# Display_Pitch.net
KiCad netlist of a schematic drawn in Altium Designer
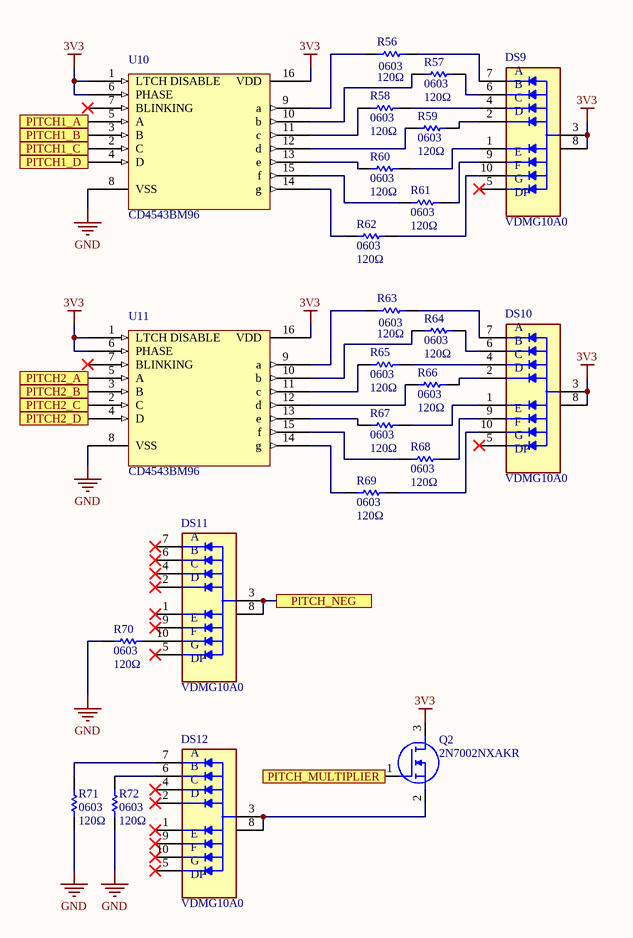
[diagram p0: Display Pitch.SchDoc]

(export (version "E")
  (design (tool "Eeschema 10.0.6"))
  (components
    (comp (ref "DS9")
      (value "VDMG10A0")
      (footprint "DISPLAY_VDMG10A0")
      (description "Smart/Normal 7 Seg Numeric LED Display")
      (fields (field (name "MANUFACTURER") "Vishay Semiconductors"))
      (libsource (lib "SKALE_LIB") (part "7 SEG DISPLAY - VDMG10A0"))
    )
    (comp (ref "DS10")
      (value "VDMG10A0")
      (footprint "DISPLAY_VDMG10A0")
      (description "Smart/Normal 7 Seg Numeric LED Display")
      (fields (field (name "MANUFACTURER") "Vishay Semiconductors"))
      (libsource (lib "SKALE_LIB") (part "7 SEG DISPLAY - VDMG10A0"))
    )
    (comp (ref "DS11")
      (value "VDMG10A0")
      (footprint "DISPLAY_VDMG10A0")
      (description "Smart/Normal 7 Seg Numeric LED Display")
      (fields (field (name "MANUFACTURER") "Vishay Semiconductors"))
      (libsource (lib "SKALE_LIB") (part "7 SEG DISPLAY - VDMG10A0"))
    )
    (comp (ref "DS12")
      (value "VDMG10A0")
      (footprint "DISPLAY_VDMG10A0")
      (description "Smart/Normal 7 Seg Numeric LED Display")
      (fields (field (name "MANUFACTURER") "Vishay Semiconductors"))
      (libsource (lib "SKALE_LIB") (part "7 SEG DISPLAY - VDMG10A0"))
    )
    (comp (ref "Q2")
      (value "2N7002NXAKR")
      (footprint "SKALE_LIB:TO-236AB")
      (description "Transistor Mosfet N-ch 60V 0.3A 3-PIN TO-263AB T/r")
      (fields (field (name "MF") "Nexperia USA Inc.") (field (name "MANUFACTURER") "Nexperia"))
      (libsource (lib "SKALE_LIB") (part "MOSFET N-60V-190mA"))
    )
    (comp (ref "R56")
      (value "120Ω")
      (footprint "RES0603")
      (description "RES 120 OHM 5% 1/10W 0603")
      (fields (field (name "PACKAGE/FOOTPRINT") "0603") (field (name "Comment") "RES_120Ω_0603"))
      (libsource (lib "SKALE_LIB") (part "RES_120Ω_0603_5%"))
    )
    (comp (ref "R57")
      (value "120Ω")
      (footprint "RES0603")
      (description "RES 120 OHM 5% 1/10W 0603")
      (fields (field (name "PACKAGE/FOOTPRINT") "0603") (field (name "Comment") "RES_120Ω_0603"))
      (libsource (lib "SKALE_LIB") (part "RES_120Ω_0603_5%"))
    )
    (comp (ref "R58")
      (value "120Ω")
      (footprint "RES0603")
      (description "RES 120 OHM 5% 1/10W 0603")
      (fields (field (name "PACKAGE/FOOTPRINT") "0603") (field (name "Comment") "RES_120Ω_0603"))
      (libsource (lib "SKALE_LIB") (part "RES_120Ω_0603_5%"))
    )
    (comp (ref "R59")
      (value "120Ω")
      (footprint "RES0603")
      (description "RES 120 OHM 5% 1/10W 0603")
      (fields (field (name "PACKAGE/FOOTPRINT") "0603") (field (name "Comment") "RES_120Ω_0603"))
      (libsource (lib "SKALE_LIB") (part "RES_120Ω_0603_5%"))
    )
    (comp (ref "R60")
      (value "120Ω")
      (footprint "RES0603")
      (description "RES 120 OHM 5% 1/10W 0603")
      (fields (field (name "PACKAGE/FOOTPRINT") "0603") (field (name "Comment") "RES_120Ω_0603"))
      (libsource (lib "SKALE_LIB") (part "RES_120Ω_0603_5%"))
    )
    (comp (ref "R61")
      (value "120Ω")
      (footprint "RES0603")
      (description "RES 120 OHM 5% 1/10W 0603")
      (fields (field (name "PACKAGE/FOOTPRINT") "0603") (field (name "Comment") "RES_120Ω_0603"))
      (libsource (lib "SKALE_LIB") (part "RES_120Ω_0603_5%"))
    )
    (comp (ref "R62")
      (value "120Ω")
      (footprint "RES0603")
      (description "RES 120 OHM 5% 1/10W 0603")
      (fields (field (name "PACKAGE/FOOTPRINT") "0603") (field (name "Comment") "RES_120Ω_0603"))
      (libsource (lib "SKALE_LIB") (part "RES_120Ω_0603_5%"))
    )
    (comp (ref "R63")
      (value "120Ω")
      (footprint "RES0603")
      (description "RES 120 OHM 5% 1/10W 0603")
      (fields (field (name "PACKAGE/FOOTPRINT") "0603") (field (name "Comment") "RES_120Ω_0603"))
      (libsource (lib "SKALE_LIB") (part "RES_120Ω_0603_5%"))
    )
    (comp (ref "R64")
      (value "120Ω")
      (footprint "RES0603")
      (description "RES 120 OHM 5% 1/10W 0603")
      (fields (field (name "PACKAGE/FOOTPRINT") "0603") (field (name "Comment") "RES_120Ω_0603"))
      (libsource (lib "SKALE_LIB") (part "RES_120Ω_0603_5%"))
    )
    (comp (ref "R65")
      (value "120Ω")
      (footprint "RES0603")
      (description "RES 120 OHM 5% 1/10W 0603")
      (fields (field (name "PACKAGE/FOOTPRINT") "0603") (field (name "Comment") "RES_120Ω_0603"))
      (libsource (lib "SKALE_LIB") (part "RES_120Ω_0603_5%"))
    )
    (comp (ref "R66")
      (value "120Ω")
      (footprint "RES0603")
      (description "RES 120 OHM 5% 1/10W 0603")
      (fields (field (name "PACKAGE/FOOTPRINT") "0603") (field (name "Comment") "RES_120Ω_0603"))
      (libsource (lib "SKALE_LIB") (part "RES_120Ω_0603_5%"))
    )
    (comp (ref "R67")
      (value "120Ω")
      (footprint "RES0603")
      (description "RES 120 OHM 5% 1/10W 0603")
      (fields (field (name "PACKAGE/FOOTPRINT") "0603") (field (name "Comment") "RES_120Ω_0603"))
      (libsource (lib "SKALE_LIB") (part "RES_120Ω_0603_5%"))
    )
    (comp (ref "R68")
      (value "120Ω")
      (footprint "RES0603")
      (description "RES 120 OHM 5% 1/10W 0603")
      (fields (field (name "PACKAGE/FOOTPRINT") "0603") (field (name "Comment") "RES_120Ω_0603"))
      (libsource (lib "SKALE_LIB") (part "RES_120Ω_0603_5%"))
    )
    (comp (ref "R69")
      (value "120Ω")
      (footprint "RES0603")
      (description "RES 120 OHM 5% 1/10W 0603")
      (fields (field (name "PACKAGE/FOOTPRINT") "0603") (field (name "Comment") "RES_120Ω_0603"))
      (libsource (lib "SKALE_LIB") (part "RES_120Ω_0603_5%"))
    )
    (comp (ref "R70")
      (value "120Ω")
      (footprint "RES0603")
      (description "RES 120 OHM 5% 1/10W 0603")
      (fields (field (name "PACKAGE/FOOTPRINT") "0603") (field (name "Comment") "RES_120Ω_0603"))
      (libsource (lib "SKALE_LIB") (part "RES_120Ω_0603_5%"))
    )
    (comp (ref "R71")
      (value "120Ω")
      (footprint "RES0603")
      (description "RES 120 OHM 5% 1/10W 0603")
      (fields (field (name "PACKAGE/FOOTPRINT") "0603") (field (name "Comment") "RES_120Ω_0603"))
      (libsource (lib "SKALE_LIB") (part "RES_120Ω_0603_5%"))
    )
    (comp (ref "R72")
      (value "120Ω")
      (footprint "RES0603")
      (description "RES 120 OHM 5% 1/10W 0603")
      (fields (field (name "PACKAGE/FOOTPRINT") "0603") (field (name "Comment") "RES_120Ω_0603"))
      (libsource (lib "SKALE_LIB") (part "RES_120Ω_0603_5%"))
    )
    (comp (ref "U10")
      (value "CD4543BM96")
      (footprint "SOIC127P600X175-16N")
      (description "Seven Segment Decoder/Driver, 4000/14000/40000 Series, Configurable Output, CMOS, PDSO16")
      (fields (field (name "MANUFACTURER") "Texas Instruments"))
      (libsource (lib "SKALE_LIB") (part "7 SEG DISPLAY IC"))
    )
    (comp (ref "U11")
      (value "CD4543BM96")
      (footprint "SOIC127P600X175-16N")
      (description "Seven Segment Decoder/Driver, 4000/14000/40000 Series, Configurable Output, CMOS, PDSO16")
      (fields (field (name "MANUFACTURER") "Texas Instruments"))
      (libsource (lib "SKALE_LIB") (part "7 SEG DISPLAY IC"))
    )
  )
  (nets
    (net (code "1") (name "/PITCH1_A") (class "Default")
      (node (ref "U10") (pin "5") (pinfunction "A_5") (pintype "input"))
    )
    (net (code "2") (name "/PITCH1_B") (class "Default")
      (node (ref "U10") (pin "3") (pinfunction "B_3") (pintype "input"))
    )
    (net (code "3") (name "/PITCH1_C") (class "Default")
      (node (ref "U10") (pin "2") (pinfunction "C_2") (pintype "input"))
    )
    (net (code "4") (name "/PITCH1_D") (class "Default")
      (node (ref "U10") (pin "4") (pinfunction "D_4") (pintype "input"))
    )
    (net (code "5") (name "/PITCH2_A") (class "Default")
      (node (ref "U11") (pin "5") (pinfunction "A_5") (pintype "input"))
    )
    (net (code "6") (name "/PITCH2_B") (class "Default")
      (node (ref "U11") (pin "3") (pinfunction "B_3") (pintype "input"))
    )
    (net (code "7") (name "/PITCH2_C") (class "Default")
      (node (ref "U11") (pin "2") (pinfunction "C_2") (pintype "input"))
    )
    (net (code "8") (name "/PITCH2_D") (class "Default")
      (node (ref "U11") (pin "4") (pinfunction "D_4") (pintype "input"))
    )
    (net (code "9") (name "/PITCH_MULTIPLIER") (class "Default")
      (node (ref "Q2") (pin "1") (pinfunction "G_1") (pintype "bidirectional"))
    )
    (net (code "10") (name "/PITCH_NEG") (class "Default")
      (node (ref "DS11") (pin "3") (pinfunction "ANODE_3") (pintype "passive"))
      (node (ref "DS11") (pin "8") (pinfunction "ANODE_8") (pintype "passive"))
    )
    (net (code "11") (name "3V3") (class "Default")
      (node (ref "DS10") (pin "3") (pinfunction "ANODE_3") (pintype "passive"))
      (node (ref "DS10") (pin "8") (pinfunction "ANODE_8") (pintype "passive"))
      (node (ref "DS9") (pin "3") (pinfunction "ANODE_3") (pintype "passive"))
      (node (ref "DS9") (pin "8") (pinfunction "ANODE_8") (pintype "passive"))
      (node (ref "Q2") (pin "3") (pinfunction "D_3") (pintype "bidirectional"))
      (node (ref "U10") (pin "1") (pinfunction "LTCH_DISABLE_1") (pintype "input"))
      (node (ref "U10") (pin "16") (pinfunction "VDD_16") (pintype "power_in"))
      (node (ref "U10") (pin "6") (pinfunction "PHASE_6") (pintype "input"))
      (node (ref "U11") (pin "1") (pinfunction "LTCH_DISABLE_1") (pintype "input"))
      (node (ref "U11") (pin "16") (pinfunction "VDD_16") (pintype "power_in"))
      (node (ref "U11") (pin "6") (pinfunction "PHASE_6") (pintype "input"))
    )
    (net (code "12") (name "GND") (class "Default")
      (node (ref "R70") (pin "1") (pinfunction "1_1") (pintype "passive"))
      (node (ref "R71") (pin "1") (pinfunction "1_1") (pintype "passive"))
      (node (ref "R72") (pin "1") (pinfunction "1_1") (pintype "passive"))
      (node (ref "U10") (pin "8") (pinfunction "VSS_8") (pintype "power_in"))
      (node (ref "U11") (pin "8") (pinfunction "VSS_8") (pintype "power_in"))
    )
    (net (code "13") (name "Net-(DS9-A)") (class "Default")
      (node (ref "DS9") (pin "7") (pinfunction "A_7") (pintype "passive"))
      (node (ref "R56") (pin "2") (pinfunction "2_2") (pintype "passive"))
    )
    (net (code "14") (name "Net-(DS9-B)") (class "Default")
      (node (ref "DS9") (pin "6") (pinfunction "B_6") (pintype "passive"))
      (node (ref "R57") (pin "2") (pinfunction "2_2") (pintype "passive"))
    )
    (net (code "15") (name "Net-(DS9-C)") (class "Default")
      (node (ref "DS9") (pin "4") (pinfunction "C_4") (pintype "passive"))
      (node (ref "R58") (pin "2") (pinfunction "2_2") (pintype "passive"))
    )
    (net (code "16") (name "Net-(DS9-D)") (class "Default")
      (node (ref "DS9") (pin "2") (pinfunction "D_2") (pintype "passive"))
      (node (ref "R59") (pin "2") (pinfunction "2_2") (pintype "passive"))
    )
    (net (code "17") (name "Net-(DS9-E)") (class "Default")
      (node (ref "DS9") (pin "1") (pinfunction "E_1") (pintype "passive"))
      (node (ref "R60") (pin "2") (pinfunction "2_2") (pintype "passive"))
    )
    (net (code "18") (name "Net-(DS9-F)") (class "Default")
      (node (ref "DS9") (pin "9") (pinfunction "F_9") (pintype "passive"))
      (node (ref "R61") (pin "2") (pinfunction "2_2") (pintype "passive"))
    )
    (net (code "19") (name "Net-(DS9-G)") (class "Default")
      (node (ref "DS9") (pin "10") (pinfunction "G_10") (pintype "passive"))
      (node (ref "R62") (pin "2") (pinfunction "2_2") (pintype "passive"))
    )
    (net (code "20") (name "Net-(DS10-A)") (class "Default")
      (node (ref "DS10") (pin "7") (pinfunction "A_7") (pintype "passive"))
      (node (ref "R63") (pin "2") (pinfunction "2_2") (pintype "passive"))
    )
    (net (code "21") (name "Net-(DS10-B)") (class "Default")
      (node (ref "DS10") (pin "6") (pinfunction "B_6") (pintype "passive"))
      (node (ref "R64") (pin "2") (pinfunction "2_2") (pintype "passive"))
    )
    (net (code "22") (name "Net-(DS10-C)") (class "Default")
      (node (ref "DS10") (pin "4") (pinfunction "C_4") (pintype "passive"))
      (node (ref "R65") (pin "2") (pinfunction "2_2") (pintype "passive"))
    )
    (net (code "23") (name "Net-(DS10-D)") (class "Default")
      (node (ref "DS10") (pin "2") (pinfunction "D_2") (pintype "passive"))
      (node (ref "R66") (pin "2") (pinfunction "2_2") (pintype "passive"))
    )
    (net (code "24") (name "Net-(DS10-E)") (class "Default")
      (node (ref "DS10") (pin "1") (pinfunction "E_1") (pintype "passive"))
      (node (ref "R67") (pin "2") (pinfunction "2_2") (pintype "passive"))
    )
    (net (code "25") (name "Net-(DS10-F)") (class "Default")
      (node (ref "DS10") (pin "9") (pinfunction "F_9") (pintype "passive"))
      (node (ref "R68") (pin "2") (pinfunction "2_2") (pintype "passive"))
    )
    (net (code "26") (name "Net-(DS10-G)") (class "Default")
      (node (ref "DS10") (pin "10") (pinfunction "G_10") (pintype "passive"))
      (node (ref "R69") (pin "2") (pinfunction "2_2") (pintype "passive"))
    )
    (net (code "27") (name "Net-(DS11-G)") (class "Default")
      (node (ref "DS11") (pin "10") (pinfunction "G_10") (pintype "passive"))
      (node (ref "R70") (pin "2") (pinfunction "2_2") (pintype "passive"))
    )
    (net (code "28") (name "Net-(DS12-A)") (class "Default")
      (node (ref "DS12") (pin "7") (pinfunction "A_7") (pintype "passive"))
      (node (ref "R71") (pin "2") (pinfunction "2_2") (pintype "passive"))
    )
    (net (code "29") (name "Net-(DS12-B)") (class "Default")
      (node (ref "DS12") (pin "6") (pinfunction "B_6") (pintype "passive"))
      (node (ref "R72") (pin "2") (pinfunction "2_2") (pintype "passive"))
    )
    (net (code "30") (name "Net-(Q2-S)") (class "Default")
      (node (ref "DS12") (pin "3") (pinfunction "ANODE_3") (pintype "passive"))
      (node (ref "DS12") (pin "8") (pinfunction "ANODE_8") (pintype "passive"))
      (node (ref "Q2") (pin "2") (pinfunction "S_2") (pintype "bidirectional"))
    )
    (net (code "31") (name "Net-(U10-a)") (class "Default")
      (node (ref "R56") (pin "1") (pinfunction "1_1") (pintype "passive"))
      (node (ref "U10") (pin "9") (pinfunction "a_9") (pintype "output"))
    )
    (net (code "32") (name "Net-(U10-b)") (class "Default")
      (node (ref "R57") (pin "1") (pinfunction "1_1") (pintype "passive"))
      (node (ref "U10") (pin "10") (pinfunction "b_10") (pintype "output"))
    )
    (net (code "33") (name "Net-(U10-c)") (class "Default")
      (node (ref "R58") (pin "1") (pinfunction "1_1") (pintype "passive"))
      (node (ref "U10") (pin "11") (pinfunction "c_11") (pintype "output"))
    )
    (net (code "34") (name "Net-(U10-d)") (class "Default")
      (node (ref "R59") (pin "1") (pinfunction "1_1") (pintype "passive"))
      (node (ref "U10") (pin "12") (pinfunction "d_12") (pintype "output"))
    )
    (net (code "35") (name "Net-(U10-e)") (class "Default")
      (node (ref "R60") (pin "1") (pinfunction "1_1") (pintype "passive"))
      (node (ref "U10") (pin "13") (pinfunction "e_13") (pintype "output"))
    )
    (net (code "36") (name "Net-(U10-f)") (class "Default")
      (node (ref "R61") (pin "1") (pinfunction "1_1") (pintype "passive"))
      (node (ref "U10") (pin "15") (pinfunction "f_15") (pintype "output"))
    )
    (net (code "37") (name "Net-(U10-g)") (class "Default")
      (node (ref "R62") (pin "1") (pinfunction "1_1") (pintype "passive"))
      (node (ref "U10") (pin "14") (pinfunction "g_14") (pintype "output"))
    )
    (net (code "38") (name "Net-(U11-a)") (class "Default")
      (node (ref "R63") (pin "1") (pinfunction "1_1") (pintype "passive"))
      (node (ref "U11") (pin "9") (pinfunction "a_9") (pintype "output"))
    )
    (net (code "39") (name "Net-(U11-b)") (class "Default")
      (node (ref "R64") (pin "1") (pinfunction "1_1") (pintype "passive"))
      (node (ref "U11") (pin "10") (pinfunction "b_10") (pintype "output"))
    )
    (net (code "40") (name "Net-(U11-c)") (class "Default")
      (node (ref "R65") (pin "1") (pinfunction "1_1") (pintype "passive"))
      (node (ref "U11") (pin "11") (pinfunction "c_11") (pintype "output"))
    )
    (net (code "41") (name "Net-(U11-d)") (class "Default")
      (node (ref "R66") (pin "1") (pinfunction "1_1") (pintype "passive"))
      (node (ref "U11") (pin "12") (pinfunction "d_12") (pintype "output"))
    )
    (net (code "42") (name "Net-(U11-e)") (class "Default")
      (node (ref "R67") (pin "1") (pinfunction "1_1") (pintype "passive"))
      (node (ref "U11") (pin "13") (pinfunction "e_13") (pintype "output"))
    )
    (net (code "43") (name "Net-(U11-f)") (class "Default")
      (node (ref "R68") (pin "1") (pinfunction "1_1") (pintype "passive"))
      (node (ref "U11") (pin "15") (pinfunction "f_15") (pintype "output"))
    )
    (net (code "44") (name "Net-(U11-g)") (class "Default")
      (node (ref "R69") (pin "1") (pinfunction "1_1") (pintype "passive"))
      (node (ref "U11") (pin "14") (pinfunction "g_14") (pintype "output"))
    )
    (net (code "45") (name "unconnected-(DS9-DP-Pad5)") (class "Default")
      (node (ref "DS9") (pin "5") (pinfunction "DP_5") (pintype "passive+no_connect"))
    )
    (net (code "46") (name "unconnected-(DS10-DP-Pad5)") (class "Default")
      (node (ref "DS10") (pin "5") (pinfunction "DP_5") (pintype "passive+no_connect"))
    )
    (net (code "47") (name "unconnected-(DS11-A-Pad7)") (class "Default")
      (node (ref "DS11") (pin "7") (pinfunction "A_7") (pintype "passive+no_connect"))
    )
    (net (code "48") (name "unconnected-(DS11-B-Pad6)") (class "Default")
      (node (ref "DS11") (pin "6") (pinfunction "B_6") (pintype "passive+no_connect"))
    )
    (net (code "49") (name "unconnected-(DS11-C-Pad4)") (class "Default")
      (node (ref "DS11") (pin "4") (pinfunction "C_4") (pintype "passive+no_connect"))
    )
    (net (code "50") (name "unconnected-(DS11-D-Pad2)") (class "Default")
      (node (ref "DS11") (pin "2") (pinfunction "D_2") (pintype "passive+no_connect"))
    )
    (net (code "51") (name "unconnected-(DS11-DP-Pad5)") (class "Default")
      (node (ref "DS11") (pin "5") (pinfunction "DP_5") (pintype "passive+no_connect"))
    )
    (net (code "52") (name "unconnected-(DS11-E-Pad1)") (class "Default")
      (node (ref "DS11") (pin "1") (pinfunction "E_1") (pintype "passive+no_connect"))
    )
    (net (code "53") (name "unconnected-(DS11-F-Pad9)") (class "Default")
      (node (ref "DS11") (pin "9") (pinfunction "F_9") (pintype "passive+no_connect"))
    )
    (net (code "54") (name "unconnected-(DS12-C-Pad4)") (class "Default")
      (node (ref "DS12") (pin "4") (pinfunction "C_4") (pintype "passive+no_connect"))
    )
    (net (code "55") (name "unconnected-(DS12-D-Pad2)") (class "Default")
      (node (ref "DS12") (pin "2") (pinfunction "D_2") (pintype "passive+no_connect"))
    )
    (net (code "56") (name "unconnected-(DS12-DP-Pad5)") (class "Default")
      (node (ref "DS12") (pin "5") (pinfunction "DP_5") (pintype "passive+no_connect"))
    )
    (net (code "57") (name "unconnected-(DS12-E-Pad1)") (class "Default")
      (node (ref "DS12") (pin "1") (pinfunction "E_1") (pintype "passive+no_connect"))
    )
    (net (code "58") (name "unconnected-(DS12-F-Pad9)") (class "Default")
      (node (ref "DS12") (pin "9") (pinfunction "F_9") (pintype "passive+no_connect"))
    )
    (net (code "59") (name "unconnected-(DS12-G-Pad10)") (class "Default")
      (node (ref "DS12") (pin "10") (pinfunction "G_10") (pintype "passive+no_connect"))
    )
    (net (code "60") (name "unconnected-(U10-BLINKING-Pad7)") (class "Default")
      (node (ref "U10") (pin "7") (pinfunction "BLINKING_7") (pintype "input+no_connect"))
    )
    (net (code "61") (name "unconnected-(U11-BLINKING-Pad7)") (class "Default")
      (node (ref "U11") (pin "7") (pinfunction "BLINKING_7") (pintype "input+no_connect"))
    )
  )
)
